# BGA_LEDs_B.net
KiCad netlist of a schematic drawn in Altium Designer
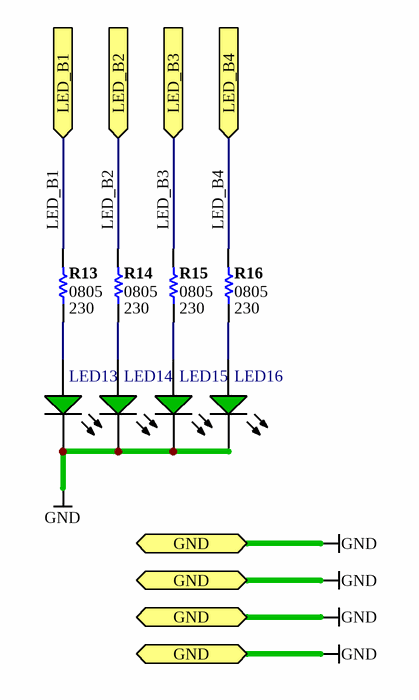
[diagram p0: BGA LEDs B.SchDoc]

(export (version "E")
  (design (tool "Eeschema 10.0.6"))
  (components
    (comp (ref "LED13")
      (value "LED_1206")
      (footprint "RESC0805(2012)70_L")
      (description "GREEN color, 1206, SMD")
      (libsource (lib "Component_DB") (part "LED_GREEN_A1K2-2.A1"))
    )
    (comp (ref "LED14")
      (value "LED_1206")
      (footprint "RESC0805(2012)70_L")
      (description "GREEN color, 1206, SMD")
      (libsource (lib "Component_DB") (part "LED_GREEN_A1K2-2.A1"))
    )
    (comp (ref "LED15")
      (value "LED_1206")
      (footprint "RESC0805(2012)70_L")
      (description "GREEN color, 1206, SMD")
      (libsource (lib "Component_DB") (part "LED_GREEN_A1K2-2.A1"))
    )
    (comp (ref "LED16")
      (value "LED_1206")
      (footprint "RESC0805(2012)70_L")
      (description "GREEN color, 1206, SMD")
      (libsource (lib "Component_DB") (part "LED_GREEN_A1K2-2.A1"))
    )
    (comp (ref "R13")
      (value "0805")
      (footprint "RESC0805(2012)70_L")
      (description "Jumper 0805 (2012 Metric)")
      (fields (field (name "VALUE (OHMS)") "230") (field (name "POWER") "None"))
      (libsource (lib "Component_DB") (part "RES"))
    )
    (comp (ref "R14")
      (value "0805")
      (footprint "RESC0805(2012)70_L")
      (description "Jumper 0805 (2012 Metric)")
      (fields (field (name "VALUE (OHMS)") "230") (field (name "POWER") "None"))
      (libsource (lib "Component_DB") (part "RES"))
    )
    (comp (ref "R15")
      (value "0805")
      (footprint "RESC0805(2012)70_L")
      (description "Jumper 0805 (2012 Metric)")
      (fields (field (name "VALUE (OHMS)") "230") (field (name "POWER") "None"))
      (libsource (lib "Component_DB") (part "RES"))
    )
    (comp (ref "R16")
      (value "0805")
      (footprint "RESC0805(2012)70_L")
      (description "Jumper 0805 (2012 Metric)")
      (fields (field (name "VALUE (OHMS)") "230") (field (name "POWER") "None"))
      (libsource (lib "Component_DB") (part "RES"))
    )
  )
  (nets
    (net (code "1") (name "/LED_B1") (class "Default")
      (node (ref "R13") (pin "2") (pinfunction "2_2") (pintype "passive"))
    )
    (net (code "2") (name "/LED_B2") (class "Default")
      (node (ref "R14") (pin "2") (pinfunction "2_2") (pintype "passive"))
    )
    (net (code "3") (name "/LED_B3") (class "Default")
      (node (ref "R15") (pin "2") (pinfunction "2_2") (pintype "passive"))
    )
    (net (code "4") (name "/LED_B4") (class "Default")
      (node (ref "R16") (pin "2") (pinfunction "2_2") (pintype "passive"))
    )
    (net (code "5") (name "GND") (class "Default")
      (node (ref "LED13") (pin "2") (pinfunction "K_2") (pintype "passive"))
      (node (ref "LED14") (pin "2") (pinfunction "K_2") (pintype "passive"))
      (node (ref "LED15") (pin "2") (pinfunction "K_2") (pintype "passive"))
      (node (ref "LED16") (pin "2") (pinfunction "K_2") (pintype "passive"))
    )
    (net (code "6") (name "Net-(LED13-A)") (class "Default")
      (node (ref "LED13") (pin "1") (pinfunction "A_1") (pintype "passive"))
      (node (ref "R13") (pin "1") (pinfunction "1_1") (pintype "passive"))
    )
    (net (code "7") (name "Net-(LED14-A)") (class "Default")
      (node (ref "LED14") (pin "1") (pinfunction "A_1") (pintype "passive"))
      (node (ref "R14") (pin "1") (pinfunction "1_1") (pintype "passive"))
    )
    (net (code "8") (name "Net-(LED15-A)") (class "Default")
      (node (ref "LED15") (pin "1") (pinfunction "A_1") (pintype "passive"))
      (node (ref "R15") (pin "1") (pinfunction "1_1") (pintype "passive"))
    )
    (net (code "9") (name "Net-(LED16-A)") (class "Default")
      (node (ref "LED16") (pin "1") (pinfunction "A_1") (pintype "passive"))
      (node (ref "R16") (pin "1") (pinfunction "1_1") (pintype "passive"))
    )
  )
)
